# camera.net
KiCad netlist of a schematic drawn in Altium Designer
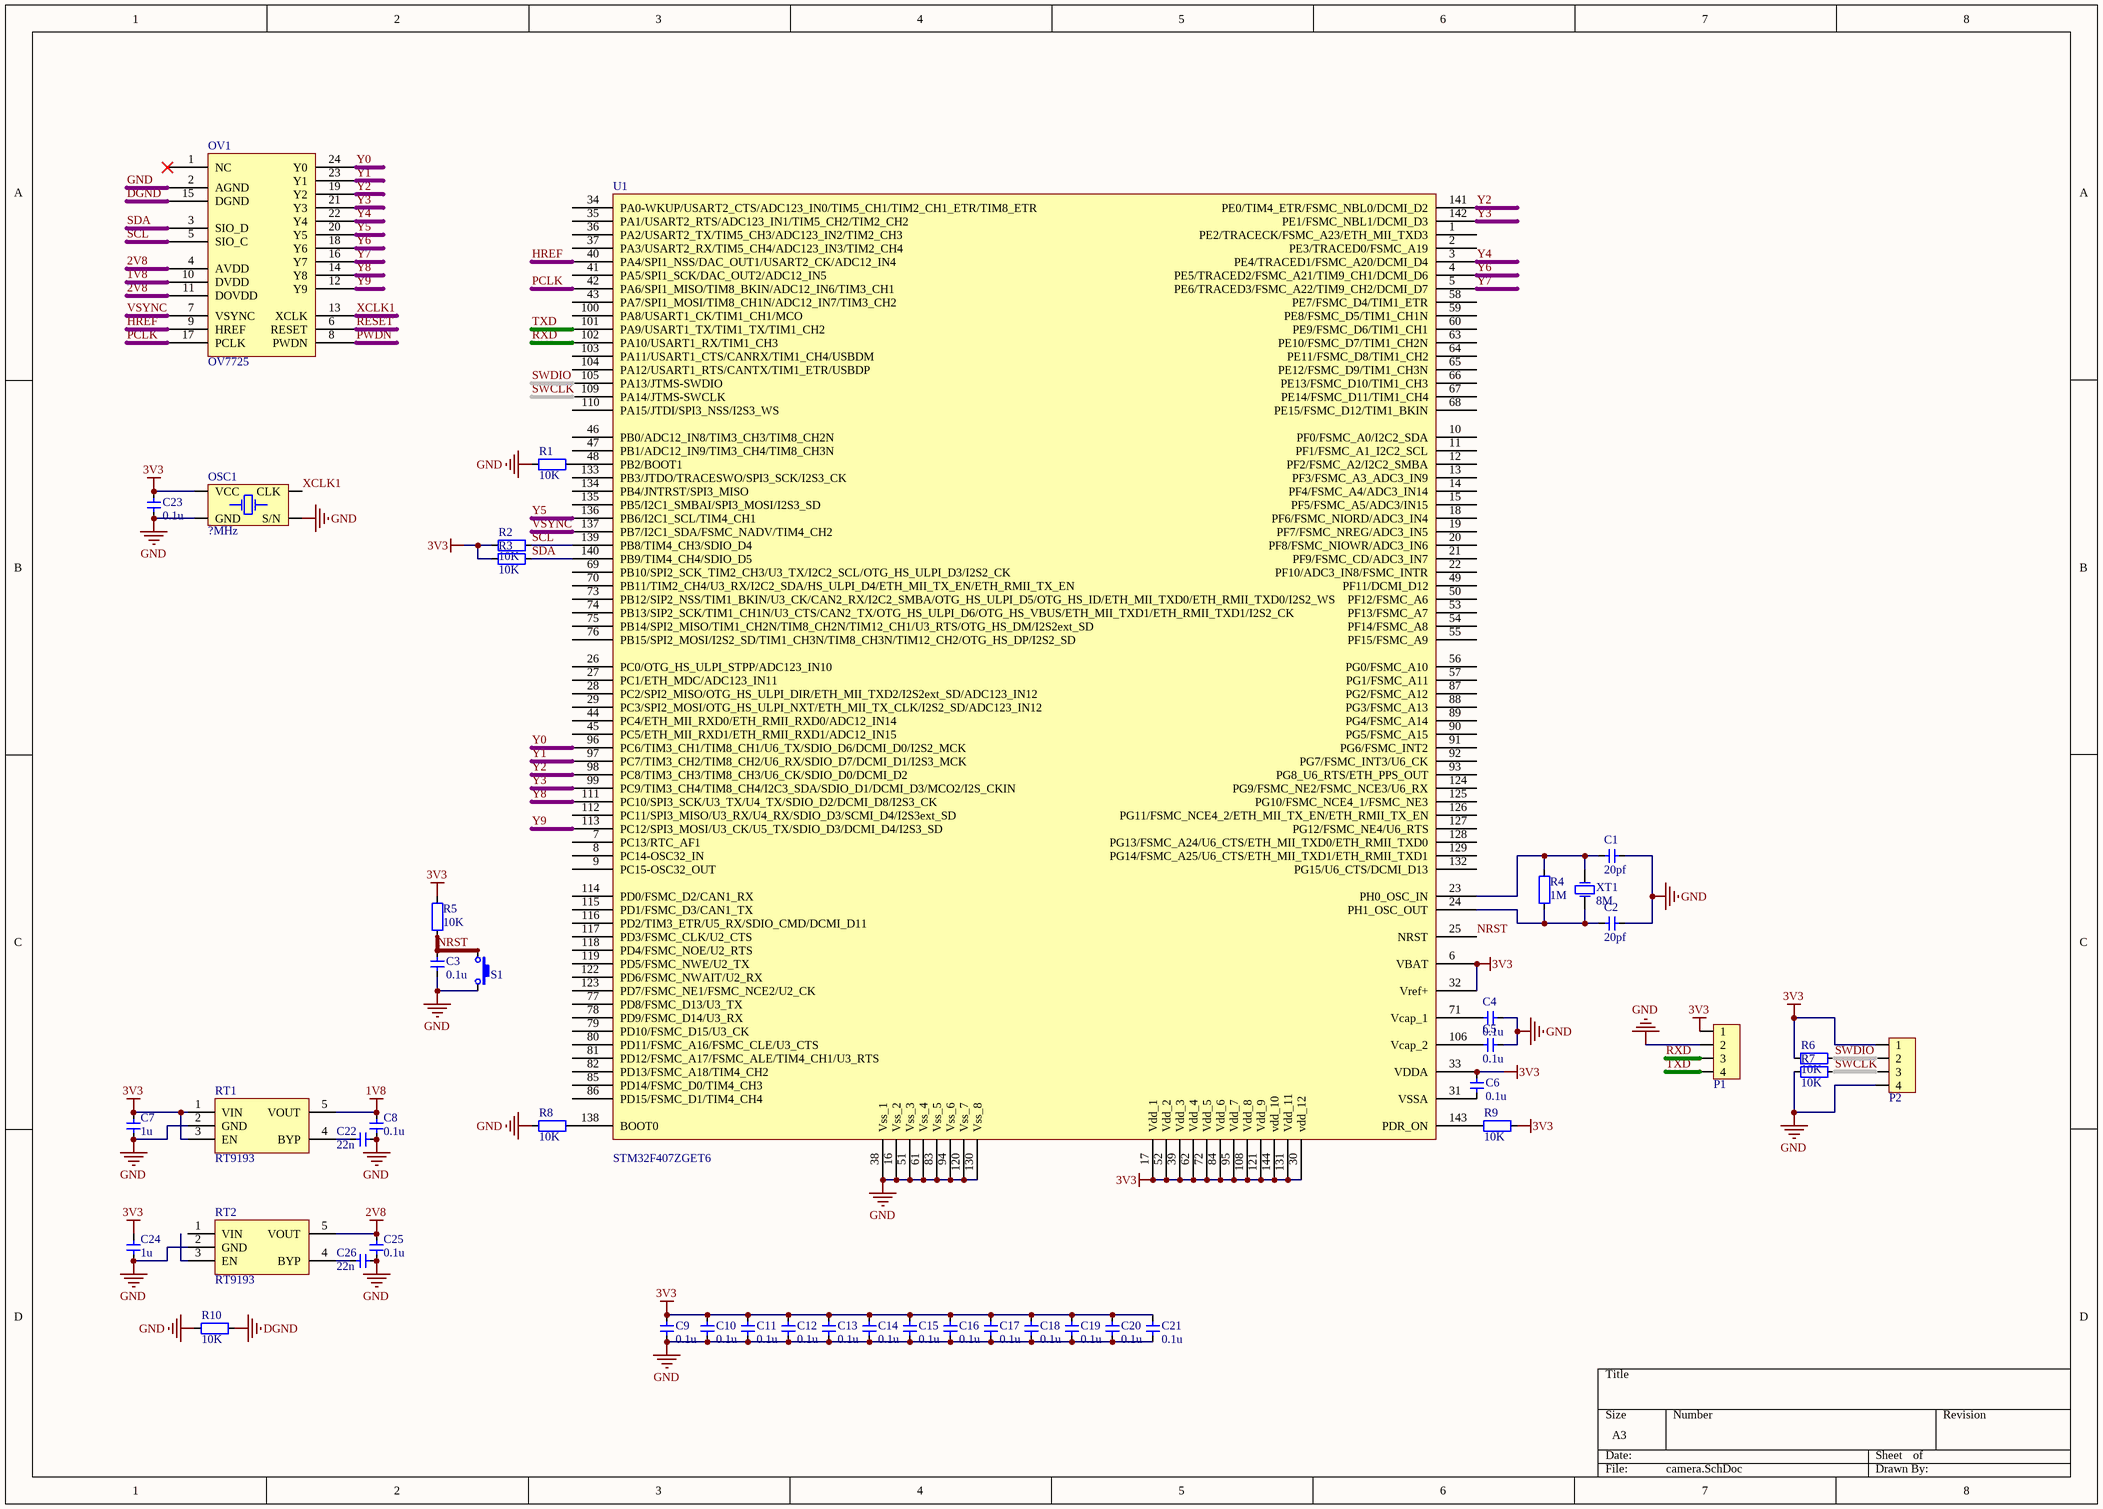
[diagram p0: camera.SchDoc]

(export (version "E")
  (design (tool "Eeschema 10.0.6"))
  (components
    (comp (ref "C1")
      (value "20pf")
      (footprint "PCB_PassiveCap:CAP_0603")
      (description "Capacitor")
      (fields (field (name "Comment") "Cap_0603"))
      (libsource (lib "SCH_Passive") (part "Cap_0603"))
    )
    (comp (ref "C2")
      (value "20pf")
      (footprint "PCB_PassiveCap:CAP_0603")
      (description "Capacitor")
      (fields (field (name "Comment") "Cap_0603"))
      (libsource (lib "SCH_Passive") (part "Cap_0603"))
    )
    (comp (ref "C3")
      (value "0.1u")
      (footprint "PCB_PassiveCap:CAP_0603")
      (description "Capacitor")
      (fields (field (name "Comment") "Cap_0603"))
      (libsource (lib "SCH_Passive") (part "Cap_0603"))
    )
    (comp (ref "C4")
      (value "0.1u")
      (footprint "PCB_PassiveCap:CAP_0603")
      (description "Capacitor")
      (fields (field (name "Comment") "Cap_0603"))
      (libsource (lib "SCH_Passive") (part "Cap_0603"))
    )
    (comp (ref "C5")
      (value "0.1u")
      (footprint "PCB_PassiveCap:CAP_0603")
      (description "Capacitor")
      (fields (field (name "Comment") "Cap_0603"))
      (libsource (lib "SCH_Passive") (part "Cap_0603"))
    )
    (comp (ref "C6")
      (value "0.1u")
      (footprint "PCB_PassiveCap:CAP_0603")
      (description "Capacitor")
      (fields (field (name "Comment") "Cap_0603"))
      (libsource (lib "SCH_Passive") (part "Cap_0603"))
    )
    (comp (ref "C7")
      (value "1u")
      (footprint "PCB_PassiveCap:CAP_0603")
      (description "Capacitor")
      (fields (field (name "Comment") "Cap_0603"))
      (libsource (lib "SCH_Passive") (part "Cap_0603"))
    )
    (comp (ref "C8")
      (value "0.1u")
      (footprint "PCB_PassiveCap:CAP_0603")
      (description "Capacitor")
      (fields (field (name "Comment") "Cap_0603"))
      (libsource (lib "SCH_Passive") (part "Cap_0603"))
    )
    (comp (ref "C9")
      (value "0.1u")
      (footprint "PCB_PassiveCap:CAP_0603")
      (description "Capacitor")
      (fields (field (name "Comment") "Cap_0603"))
      (libsource (lib "SCH_Passive") (part "Cap_0603"))
    )
    (comp (ref "C10")
      (value "0.1u")
      (footprint "PCB_PassiveCap:CAP_0603")
      (description "Capacitor")
      (fields (field (name "Comment") "Cap_0603"))
      (libsource (lib "SCH_Passive") (part "Cap_0603"))
    )
    (comp (ref "C11")
      (value "0.1u")
      (footprint "PCB_PassiveCap:CAP_0603")
      (description "Capacitor")
      (fields (field (name "Comment") "Cap_0603"))
      (libsource (lib "SCH_Passive") (part "Cap_0603"))
    )
    (comp (ref "C12")
      (value "0.1u")
      (footprint "PCB_PassiveCap:CAP_0603")
      (description "Capacitor")
      (fields (field (name "Comment") "Cap_0603"))
      (libsource (lib "SCH_Passive") (part "Cap_0603"))
    )
    (comp (ref "C13")
      (value "0.1u")
      (footprint "PCB_PassiveCap:CAP_0603")
      (description "Capacitor")
      (fields (field (name "Comment") "Cap_0603"))
      (libsource (lib "SCH_Passive") (part "Cap_0603"))
    )
    (comp (ref "C14")
      (value "0.1u")
      (footprint "PCB_PassiveCap:CAP_0603")
      (description "Capacitor")
      (fields (field (name "Comment") "Cap_0603"))
      (libsource (lib "SCH_Passive") (part "Cap_0603"))
    )
    (comp (ref "C15")
      (value "0.1u")
      (footprint "PCB_PassiveCap:CAP_0603")
      (description "Capacitor")
      (fields (field (name "Comment") "Cap_0603"))
      (libsource (lib "SCH_Passive") (part "Cap_0603"))
    )
    (comp (ref "C16")
      (value "0.1u")
      (footprint "PCB_PassiveCap:CAP_0603")
      (description "Capacitor")
      (fields (field (name "Comment") "Cap_0603"))
      (libsource (lib "SCH_Passive") (part "Cap_0603"))
    )
    (comp (ref "C17")
      (value "0.1u")
      (footprint "PCB_PassiveCap:CAP_0603")
      (description "Capacitor")
      (fields (field (name "Comment") "Cap_0603"))
      (libsource (lib "SCH_Passive") (part "Cap_0603"))
    )
    (comp (ref "C18")
      (value "0.1u")
      (footprint "PCB_PassiveCap:CAP_0603")
      (description "Capacitor")
      (fields (field (name "Comment") "Cap_0603"))
      (libsource (lib "SCH_Passive") (part "Cap_0603"))
    )
    (comp (ref "C19")
      (value "0.1u")
      (footprint "PCB_PassiveCap:CAP_0603")
      (description "Capacitor")
      (fields (field (name "Comment") "Cap_0603"))
      (libsource (lib "SCH_Passive") (part "Cap_0603"))
    )
    (comp (ref "C20")
      (value "0.1u")
      (footprint "PCB_PassiveCap:CAP_0603")
      (description "Capacitor")
      (fields (field (name "Comment") "Cap_0603"))
      (libsource (lib "SCH_Passive") (part "Cap_0603"))
    )
    (comp (ref "C21")
      (value "0.1u")
      (footprint "PCB_PassiveCap:CAP_0603")
      (description "Capacitor")
      (fields (field (name "Comment") "Cap_0603"))
      (libsource (lib "SCH_Passive") (part "Cap_0603"))
    )
    (comp (ref "C22")
      (value "22n")
      (footprint "PCB_PassiveCap:CAP_0603")
      (description "Capacitor")
      (fields (field (name "Comment") "Cap_0603"))
      (libsource (lib "SCH_Passive") (part "Cap_0603"))
    )
    (comp (ref "C23")
      (value "0.1u")
      (footprint "PCB_PassiveCap:CAP_0603")
      (description "Capacitor")
      (fields (field (name "Comment") "Cap_0603"))
      (libsource (lib "SCH_Passive") (part "Cap_0603"))
    )
    (comp (ref "C24")
      (value "1u")
      (footprint "PCB_PassiveCap:CAP_0603")
      (description "Capacitor")
      (fields (field (name "Comment") "Cap_0603"))
      (libsource (lib "SCH_Passive") (part "Cap_0603"))
    )
    (comp (ref "C25")
      (value "0.1u")
      (footprint "PCB_PassiveCap:CAP_0603")
      (description "Capacitor")
      (fields (field (name "Comment") "Cap_0603"))
      (libsource (lib "SCH_Passive") (part "Cap_0603"))
    )
    (comp (ref "C26")
      (value "22n")
      (footprint "PCB_PassiveCap:CAP_0603")
      (description "Capacitor")
      (fields (field (name "Comment") "Cap_0603"))
      (libsource (lib "SCH_Passive") (part "Cap_0603"))
    )
    (comp (ref "OSC1")
      (value "?MHz")
      (footprint "PCB_Oscillator:XT_3225_4")
      (description "Crystal Oscillator")
      (fields (field (name "Comment") "OSC_3225_4P"))
      (libsource (lib "SCH_Oscillator") (part "OSC_3225_4P"))
    )
    (comp (ref "OV1")
      (value "OV7725")
      (footprint "ov7725")
      (libsource (lib "SCH_IntegratedCircuit") (part "OV7725"))
    )
    (comp (ref "P1")
      (value "HDR1x4_2.54")
      (footprint "PCB_ConnectorHDR:HDR1X4_2.54_90")
      (description "Header")
      (libsource (lib "SCH_ConnectorHDR") (part "HDR1x4_2.54"))
    )
    (comp (ref "P2")
      (value "HDR1x4_2.54")
      (footprint "PCB_ConnectorHDR:HDR1X4_2.54_90")
      (description "Header")
      (libsource (lib "SCH_ConnectorHDR") (part "HDR1x4_2.54"))
    )
    (comp (ref "R1")
      (value "10K")
      (footprint "PCB_PassiveRes:RES_0603")
      (description "Resistor")
      (fields (field (name "Comment") "Res_0603"))
      (libsource (lib "") (part "Res_0603_2"))
    )
    (comp (ref "R2")
      (value "10K")
      (footprint "PCB_PassiveRes:RES_0603")
      (description "Resistor")
      (fields (field (name "Comment") "Res_0603"))
      (libsource (lib "") (part "Res_0603_1"))
    )
    (comp (ref "R3")
      (value "10K")
      (footprint "PCB_PassiveRes:RES_0603")
      (description "Resistor")
      (fields (field (name "Comment") "Res_0603"))
      (libsource (lib "") (part "Res_0603_1"))
    )
    (comp (ref "R4")
      (value "1M")
      (footprint "PCB_PassiveRes:RES_0603")
      (description "Resistor")
      (fields (field (name "Comment") "Res_0603"))
      (libsource (lib "SCH_Passive") (part "Res_0603"))
    )
    (comp (ref "R5")
      (value "10K")
      (footprint "PCB_PassiveRes:RES_0603")
      (description "Resistor")
      (fields (field (name "Comment") "Res_0603"))
      (libsource (lib "SCH_Passive") (part "Res_0603"))
    )
    (comp (ref "R6")
      (value "10K")
      (footprint "PCB_PassiveRes:RES_0603")
      (description "Resistor")
      (fields (field (name "Comment") "Res_0603"))
      (libsource (lib "") (part "Res_0603_2"))
    )
    (comp (ref "R7")
      (value "10K")
      (footprint "PCB_PassiveRes:RES_0603")
      (description "Resistor")
      (fields (field (name "Comment") "Res_0603"))
      (libsource (lib "") (part "Res_0603_2"))
    )
    (comp (ref "R8")
      (value "10K")
      (footprint "PCB_PassiveRes:RES_0603")
      (description "Resistor")
      (fields (field (name "Comment") "Res_0603"))
      (libsource (lib "") (part "Res_0603_1"))
    )
    (comp (ref "R9")
      (value "10K")
      (footprint "PCB_PassiveRes:RES_0603")
      (description "Resistor")
      (fields (field (name "Comment") "Res_0603"))
      (libsource (lib "") (part "Res_0603_1"))
    )
    (comp (ref "R10")
      (value "10K")
      (footprint "PCB_PassiveRes:RES_0603")
      (description "Resistor")
      (fields (field (name "Comment") "Res_0603"))
      (libsource (lib "") (part "Res_0603_1"))
    )
    (comp (ref "RT1")
      (value "RT9193")
      (footprint "PCB_IntegratedCircuit:SOT23-5")
      (description "Power")
      (libsource (lib "SCH_IntegratedCircuit") (part "RT9193"))
    )
    (comp (ref "RT2")
      (value "RT9193")
      (footprint "PCB_IntegratedCircuit:SOT23-5")
      (description "Power")
      (libsource (lib "SCH_IntegratedCircuit") (part "RT9193"))
    )
    (comp (ref "S1")
      (value "ButtonTACT_3x4x2_180")
      (footprint "PCB_Switch:ButtonTACT_3x4x2_180H")
      (description "Button")
      (libsource (lib "SCH_Switch") (part "ButtonTACT_3x4x2_180"))
    )
    (comp (ref "U1")
      (value "STM32F407ZGET6")
      (footprint "LQFP_P0.5_144")
      (libsource (lib "STM32F407VGT6") (part "Component_1"))
    )
    (comp (ref "XT1")
      (value "8M")
      (footprint "PCB_Oscillator:XT_5032_2")
      (description "Crystal Oscillator")
      (fields (field (name "Comment") "XTAL_5032_2P"))
      (libsource (lib "SCH_Oscillator") (part "XTAL_5032_2P"))
    )
  )
  (nets
    (net (code "1") (name "/HREF") (class "Default")
      (node (ref "OV1") (pin "9") (pinfunction "HREF_9") (pintype "passive"))
      (node (ref "U1") (pin "40") (pinfunction "PA4/SPI1_NSS/DAC_OUT1/USART2_CK/ADC12_IN4_40") (pintype "passive"))
    )
    (net (code "2") (name "/NRST") (class "Default")
      (node (ref "C3") (pin "2") (pinfunction "2_2") (pintype "passive"))
      (node (ref "R5") (pin "2") (pinfunction "2_2") (pintype "passive"))
      (node (ref "S1") (pin "1") (pinfunction "1_1") (pintype "passive"))
      (node (ref "U1") (pin "25") (pinfunction "NRST_25") (pintype "passive"))
    )
    (net (code "3") (name "/PCLK") (class "Default")
      (node (ref "OV1") (pin "17") (pinfunction "PCLK_17") (pintype "passive"))
      (node (ref "U1") (pin "42") (pinfunction "PA6/SPI1_MISO/TIM8_BKIN/ADC12_IN6/TIM3_CH1_42") (pintype "passive"))
    )
    (net (code "4") (name "/PWDN") (class "Default")
      (node (ref "OV1") (pin "8") (pinfunction "PWDN_8") (pintype "passive"))
    )
    (net (code "5") (name "/RESET") (class "Default")
      (node (ref "OV1") (pin "6") (pinfunction "RESET_6") (pintype "passive"))
    )
    (net (code "6") (name "/RXD") (class "Default")
      (node (ref "P1") (pin "3") (pinfunction "3_3") (pintype "passive"))
      (node (ref "U1") (pin "102") (pinfunction "PA10/USART1_RX/TIM1_CH3_102") (pintype "passive"))
    )
    (net (code "7") (name "/SCL") (class "Default")
      (node (ref "OV1") (pin "5") (pinfunction "SIO_C_5") (pintype "passive"))
      (node (ref "R2") (pin "2") (pinfunction "2_2") (pintype "passive"))
      (node (ref "U1") (pin "139") (pinfunction "PB8/TIM4_CH3/SDIO_D4_139") (pintype "passive"))
    )
    (net (code "8") (name "/SDA") (class "Default")
      (node (ref "OV1") (pin "3") (pinfunction "SIO_D_3") (pintype "passive"))
      (node (ref "R3") (pin "2") (pinfunction "2_2") (pintype "passive"))
      (node (ref "U1") (pin "140") (pinfunction "PB9/TIM4_CH4/SDIO_D5_140") (pintype "passive"))
    )
    (net (code "9") (name "/SWCLK") (class "Default")
      (node (ref "P2") (pin "3") (pinfunction "3_3") (pintype "passive"))
      (node (ref "R7") (pin "1") (pinfunction "1_1") (pintype "passive"))
      (node (ref "U1") (pin "109") (pinfunction "PA14/JTMS-SWCLK_109") (pintype "passive"))
    )
    (net (code "10") (name "/SWDIO") (class "Default")
      (node (ref "P2") (pin "2") (pinfunction "2_2") (pintype "passive"))
      (node (ref "R6") (pin "1") (pinfunction "1_1") (pintype "passive"))
      (node (ref "U1") (pin "105") (pinfunction "PA13/JTMS-SWDIO_105") (pintype "passive"))
    )
    (net (code "11") (name "/TXD") (class "Default")
      (node (ref "P1") (pin "4") (pinfunction "4_4") (pintype "passive"))
      (node (ref "U1") (pin "101") (pinfunction "PA9/USART1_TX/TIM1_TX/TIM1_CH2_101") (pintype "passive"))
    )
    (net (code "12") (name "/VSYNC") (class "Default")
      (node (ref "OV1") (pin "7") (pinfunction "VSYNC_7") (pintype "passive"))
      (node (ref "U1") (pin "137") (pinfunction "PB7/I2C1_SDA/FSMC_NADV/TIM4_CH2_137") (pintype "passive"))
    )
    (net (code "13") (name "/XCLK1") (class "Default")
      (node (ref "OSC1") (pin "3") (pinfunction "CLK_3") (pintype "passive"))
      (node (ref "OV1") (pin "13") (pinfunction "XCLK_13") (pintype "passive"))
    )
    (net (code "14") (name "/Y0") (class "Default")
      (node (ref "OV1") (pin "24") (pinfunction "Y0_24") (pintype "passive"))
      (node (ref "U1") (pin "96") (pinfunction "PC6/TIM3_CH1/TIM8_CH1/U6_TX/SDIO_D6/DCMI_D0/I2S2_MCK_96") (pintype "passive"))
    )
    (net (code "15") (name "/Y1") (class "Default")
      (node (ref "OV1") (pin "23") (pinfunction "Y1_23") (pintype "passive"))
      (node (ref "U1") (pin "97") (pinfunction "PC7/TIM3_CH2/TIM8_CH2/U6_RX/SDIO_D7/DCMI_D1/I2S3_MCK_97") (pintype "passive"))
    )
    (net (code "16") (name "/Y2") (class "Default")
      (node (ref "OV1") (pin "19") (pinfunction "Y2_19") (pintype "passive"))
      (node (ref "U1") (pin "141") (pinfunction "PE0/TIM4_ETR/FSMC_NBL0/DCMI_D2_141") (pintype "passive"))
      (node (ref "U1") (pin "98") (pinfunction "PC8/TIM3_CH3/TIM8_CH3/U6_CK/SDIO_D0/DCMI_D2_98") (pintype "passive"))
    )
    (net (code "17") (name "/Y3") (class "Default")
      (node (ref "OV1") (pin "21") (pinfunction "Y3_21") (pintype "passive"))
      (node (ref "U1") (pin "142") (pinfunction "PE1/FSMC_NBL1/DCMI_D3_142") (pintype "passive"))
      (node (ref "U1") (pin "99") (pinfunction "PC9/TIM3_CH4/TIM8_CH4/I2C3_SDA/SDIO_D1/DCMI_D3/MCO2/I2S_CKIN_99") (pintype "passive"))
    )
    (net (code "18") (name "/Y4") (class "Default")
      (node (ref "OV1") (pin "22") (pinfunction "Y4_22") (pintype "passive"))
      (node (ref "U1") (pin "3") (pinfunction "PE4/TRACED1/FSMC_A20/DCMI_D4_3") (pintype "passive"))
    )
    (net (code "19") (name "/Y5") (class "Default")
      (node (ref "OV1") (pin "20") (pinfunction "Y5_20") (pintype "passive"))
      (node (ref "U1") (pin "136") (pinfunction "PB6/I2C1_SCL/TIM4_CH1_136") (pintype "passive"))
    )
    (net (code "20") (name "/Y6") (class "Default")
      (node (ref "OV1") (pin "18") (pinfunction "Y6_18") (pintype "passive"))
      (node (ref "U1") (pin "4") (pinfunction "PE5/TRACED2/FSMC_A21/TIM9_CH1/DCMI_D6_4") (pintype "passive"))
    )
    (net (code "21") (name "/Y7") (class "Default")
      (node (ref "OV1") (pin "16") (pinfunction "Y7_16") (pintype "passive"))
      (node (ref "U1") (pin "5") (pinfunction "PE6/TRACED3/FSMC_A22/TIM9_CH2/DCMI_D7_5") (pintype "passive"))
    )
    (net (code "22") (name "/Y8") (class "Default")
      (node (ref "OV1") (pin "14") (pinfunction "Y8_14") (pintype "passive"))
      (node (ref "U1") (pin "111") (pinfunction "PC10/SPI3_SCK/U3_TX/U4_TX/SDIO_D2/DCMI_D8/I2S3_CK_111") (pintype "passive"))
    )
    (net (code "23") (name "/Y9") (class "Default")
      (node (ref "OV1") (pin "12") (pinfunction "Y9_12") (pintype "passive"))
      (node (ref "U1") (pin "113") (pinfunction "PC12/SPI3_MOSI/U3_CK/U5_TX/SDIO_D3/DCMI_D4/I2S3_SD_113") (pintype "passive"))
    )
    (net (code "24") (name "1V8") (class "Default")
      (node (ref "C8") (pin "2") (pinfunction "2_2") (pintype "passive"))
      (node (ref "OV1") (pin "10") (pinfunction "DVDD_10") (pintype "passive"))
      (node (ref "RT1") (pin "5") (pinfunction "VOUT_5") (pintype "passive"))
    )
    (net (code "25") (name "2V8") (class "Default")
      (node (ref "C25") (pin "2") (pinfunction "2_2") (pintype "passive"))
      (node (ref "OV1") (pin "11") (pinfunction "DOVDD_11") (pintype "passive"))
      (node (ref "OV1") (pin "4") (pinfunction "AVDD_4") (pintype "passive"))
      (node (ref "RT2") (pin "5") (pinfunction "VOUT_5") (pintype "passive"))
    )
    (net (code "26") (name "3V3") (class "Default")
      (node (ref "C10") (pin "2") (pinfunction "2_2") (pintype "passive"))
      (node (ref "C11") (pin "2") (pinfunction "2_2") (pintype "passive"))
      (node (ref "C12") (pin "2") (pinfunction "2_2") (pintype "passive"))
      (node (ref "C13") (pin "2") (pinfunction "2_2") (pintype "passive"))
      (node (ref "C14") (pin "2") (pinfunction "2_2") (pintype "passive"))
      (node (ref "C15") (pin "2") (pinfunction "2_2") (pintype "passive"))
      (node (ref "C16") (pin "2") (pinfunction "2_2") (pintype "passive"))
      (node (ref "C17") (pin "2") (pinfunction "2_2") (pintype "passive"))
      (node (ref "C18") (pin "2") (pinfunction "2_2") (pintype "passive"))
      (node (ref "C19") (pin "2") (pinfunction "2_2") (pintype "passive"))
      (node (ref "C20") (pin "2") (pinfunction "2_2") (pintype "passive"))
      (node (ref "C21") (pin "2") (pinfunction "2_2") (pintype "passive"))
      (node (ref "C23") (pin "2") (pinfunction "2_2") (pintype "passive"))
      (node (ref "C24") (pin "2") (pinfunction "2_2") (pintype "passive"))
      (node (ref "C6") (pin "1") (pinfunction "1_1") (pintype "passive"))
      (node (ref "C7") (pin "2") (pinfunction "2_2") (pintype "passive"))
      (node (ref "C9") (pin "2") (pinfunction "2_2") (pintype "passive"))
      (node (ref "OSC1") (pin "4") (pinfunction "VCC_4") (pintype "passive"))
      (node (ref "P1") (pin "1") (pinfunction "1_1") (pintype "passive"))
      (node (ref "P2") (pin "1") (pinfunction "1_1") (pintype "passive"))
      (node (ref "R2") (pin "1") (pinfunction "1_1") (pintype "passive"))
      (node (ref "R3") (pin "1") (pinfunction "1_1") (pintype "passive"))
      (node (ref "R5") (pin "1") (pinfunction "1_1") (pintype "passive"))
      (node (ref "R6") (pin "2") (pinfunction "2_2") (pintype "passive"))
      (node (ref "R9") (pin "2") (pinfunction "2_2") (pintype "passive"))
      (node (ref "RT1") (pin "1") (pinfunction "VIN_1") (pintype "passive"))
      (node (ref "RT1") (pin "3") (pinfunction "EN_3") (pintype "power_in"))
      (node (ref "U1") (pin "108") (pinfunction "Vdd_8_108") (pintype "passive"))
      (node (ref "U1") (pin "121") (pinfunction "Vdd_9_121") (pintype "passive"))
      (node (ref "U1") (pin "131") (pinfunction "Vdd_11_131") (pintype "passive"))
      (node (ref "U1") (pin "144") (pinfunction "vdd_10_144") (pintype "passive"))
      (node (ref "U1") (pin "17") (pinfunction "Vdd_1_17") (pintype "passive"))
      (node (ref "U1") (pin "30") (pinfunction "vdd_12_30") (pintype "passive"))
      (node (ref "U1") (pin "32") (pinfunction "Vref+_32") (pintype "passive"))
      (node (ref "U1") (pin "33") (pinfunction "VDDA_33") (pintype "passive"))
      (node (ref "U1") (pin "39") (pinfunction "Vdd_3_39") (pintype "passive"))
      (node (ref "U1") (pin "52") (pinfunction "Vdd_2_52") (pintype "passive"))
      (node (ref "U1") (pin "6") (pinfunction "VBAT_6") (pintype "passive"))
      (node (ref "U1") (pin "62") (pinfunction "Vdd_4_62") (pintype "passive"))
      (node (ref "U1") (pin "72") (pinfunction "Vdd_5_72") (pintype "passive"))
      (node (ref "U1") (pin "84") (pinfunction "Vdd_6_84") (pintype "passive"))
      (node (ref "U1") (pin "95") (pinfunction "Vdd_7_95") (pintype "passive"))
    )
    (net (code "27") (name "DGND") (class "Default")
      (node (ref "OV1") (pin "15") (pinfunction "DGND_15") (pintype "passive"))
      (node (ref "R10") (pin "2") (pinfunction "2_2") (pintype "passive"))
    )
    (net (code "28") (name "GND") (class "Default")
      (node (ref "C1") (pin "1") (pinfunction "1_1") (pintype "passive"))
      (node (ref "C10") (pin "1") (pinfunction "1_1") (pintype "passive"))
      (node (ref "C11") (pin "1") (pinfunction "1_1") (pintype "passive"))
      (node (ref "C12") (pin "1") (pinfunction "1_1") (pintype "passive"))
      (node (ref "C13") (pin "1") (pinfunction "1_1") (pintype "passive"))
      (node (ref "C14") (pin "1") (pinfunction "1_1") (pintype "passive"))
      (node (ref "C15") (pin "1") (pinfunction "1_1") (pintype "passive"))
      (node (ref "C16") (pin "1") (pinfunction "1_1") (pintype "passive"))
      (node (ref "C17") (pin "1") (pinfunction "1_1") (pintype "passive"))
      (node (ref "C18") (pin "1") (pinfunction "1_1") (pintype "passive"))
      (node (ref "C19") (pin "1") (pinfunction "1_1") (pintype "passive"))
      (node (ref "C2") (pin "1") (pinfunction "1_1") (pintype "passive"))
      (node (ref "C20") (pin "1") (pinfunction "1_1") (pintype "passive"))
      (node (ref "C21") (pin "1") (pinfunction "1_1") (pintype "passive"))
      (node (ref "C22") (pin "1") (pinfunction "1_1") (pintype "passive"))
      (node (ref "C23") (pin "1") (pinfunction "1_1") (pintype "passive"))
      (node (ref "C24") (pin "1") (pinfunction "1_1") (pintype "passive"))
      (node (ref "C25") (pin "1") (pinfunction "1_1") (pintype "passive"))
      (node (ref "C26") (pin "1") (pinfunction "1_1") (pintype "passive"))
      (node (ref "C3") (pin "1") (pinfunction "1_1") (pintype "passive"))
      (node (ref "C4") (pin "1") (pinfunction "1_1") (pintype "passive"))
      (node (ref "C5") (pin "1") (pinfunction "1_1") (pintype "passive"))
      (node (ref "C7") (pin "1") (pinfunction "1_1") (pintype "passive"))
      (node (ref "C8") (pin "1") (pinfunction "1_1") (pintype "passive"))
      (node (ref "C9") (pin "1") (pinfunction "1_1") (pintype "passive"))
      (node (ref "OSC1") (pin "1") (pinfunction "S/N_1") (pintype "passive"))
      (node (ref "OSC1") (pin "2") (pinfunction "GND_2") (pintype "passive"))
      (node (ref "OV1") (pin "2") (pinfunction "AGND_2") (pintype "passive"))
      (node (ref "P1") (pin "2") (pinfunction "2_2") (pintype "passive"))
      (node (ref "P2") (pin "4") (pinfunction "4_4") (pintype "passive"))
      (node (ref "R1") (pin "2") (pinfunction "2_2") (pintype "passive"))
      (node (ref "R10") (pin "1") (pinfunction "1_1") (pintype "passive"))
      (node (ref "R7") (pin "2") (pinfunction "2_2") (pintype "passive"))
      (node (ref "R8") (pin "1") (pinfunction "1_1") (pintype "passive"))
      (node (ref "RT1") (pin "2") (pinfunction "GND_2") (pintype "passive"))
      (node (ref "RT2") (pin "2") (pinfunction "GND_2") (pintype "passive"))
      (node (ref "S1") (pin "2") (pinfunction "2_2") (pintype "passive"))
      (node (ref "U1") (pin "120") (pinfunction "Vss_7_120") (pintype "passive"))
      (node (ref "U1") (pin "130") (pinfunction "Vss_8_130") (pintype "passive"))
      (node (ref "U1") (pin "16") (pinfunction "Vss_2_16") (pintype "passive"))
      (node (ref "U1") (pin "38") (pinfunction "Vss_1_38") (pintype "passive"))
      (node (ref "U1") (pin "51") (pinfunction "Vss_3_51") (pintype "passive"))
      (node (ref "U1") (pin "61") (pinfunction "Vss_4_61") (pintype "passive"))
      (node (ref "U1") (pin "83") (pinfunction "Vss_5_83") (pintype "passive"))
      (node (ref "U1") (pin "94") (pinfunction "Vss_6_94") (pintype "passive"))
    )
    (net (code "29") (name "Net-(RT1-BYP)") (class "Default")
      (node (ref "C22") (pin "2") (pinfunction "2_2") (pintype "passive"))
      (node (ref "RT1") (pin "4") (pinfunction "BYP_4") (pintype "passive"))
    )
    (net (code "30") (name "Net-(RT2-BYP)") (class "Default")
      (node (ref "C26") (pin "2") (pinfunction "2_2") (pintype "passive"))
      (node (ref "RT2") (pin "4") (pinfunction "BYP_4") (pintype "passive"))
    )
    (net (code "31") (name "Net-(U1-BOOT0)") (class "Default")
      (node (ref "R8") (pin "2") (pinfunction "2_2") (pintype "passive"))
      (node (ref "U1") (pin "138") (pinfunction "BOOT0_138") (pintype "passive"))
    )
    (net (code "32") (name "Net-(U1-PB2{slash}BOOT1)") (class "Default")
      (node (ref "R1") (pin "1") (pinfunction "1_1") (pintype "passive"))
      (node (ref "U1") (pin "48") (pinfunction "PB2/BOOT1_48") (pintype "passive"))
    )
    (net (code "33") (name "Net-(U1-PDR_ON)") (class "Default")
      (node (ref "R9") (pin "1") (pinfunction "1_1") (pintype "passive"))
      (node (ref "U1") (pin "143") (pinfunction "PDR_ON_143") (pintype "passive"))
    )
    (net (code "34") (name "Net-(U1-PH0_OSC_IN)") (class "Default")
      (node (ref "C1") (pin "2") (pinfunction "2_2") (pintype "passive"))
      (node (ref "R4") (pin "1") (pinfunction "1_1") (pintype "passive"))
      (node (ref "U1") (pin "23") (pinfunction "PH0_OSC_IN_23") (pintype "passive"))
      (node (ref "XT1") (pin "1") (pinfunction "OSC1_1") (pintype "passive"))
    )
    (net (code "35") (name "Net-(U1-PH1_OSC_OUT)") (class "Default")
      (node (ref "C2") (pin "2") (pinfunction "2_2") (pintype "passive"))
      (node (ref "R4") (pin "2") (pinfunction "2_2") (pintype "passive"))
      (node (ref "U1") (pin "24") (pinfunction "PH1_OSC_OUT_24") (pintype "passive"))
      (node (ref "XT1") (pin "2") (pinfunction "OSC2_2") (pintype "passive"))
    )
    (net (code "36") (name "Net-(U1-VSSA)") (class "Default")
      (node (ref "C6") (pin "2") (pinfunction "2_2") (pintype "passive"))
      (node (ref "U1") (pin "31") (pinfunction "VSSA_31") (pintype "passive"))
    )
    (net (code "37") (name "Net-(U1-Vcap_1)") (class "Default")
      (node (ref "C4") (pin "2") (pinfunction "2_2") (pintype "passive"))
      (node (ref "U1") (pin "71") (pinfunction "Vcap_1_71") (pintype "passive"))
    )
    (net (code "38") (name "Net-(U1-Vcap_2)") (class "Default")
      (node (ref "C5") (pin "2") (pinfunction "2_2") (pintype "passive"))
      (node (ref "U1") (pin "106") (pinfunction "Vcap_2_106") (pintype "passive"))
    )
    (net (code "39") (name "unconnected-(OV1-NC-Pad1)") (class "Default")
      (node (ref "OV1") (pin "1") (pinfunction "NC_1") (pintype "passive+no_connect"))
    )
    (net (code "40") (name "unconnected-(RT2-EN-Pad3)") (class "Default")
      (node (ref "RT2") (pin "3") (pinfunction "EN_3") (pintype "power_in"))
    )
    (net (code "41") (name "unconnected-(RT2-VIN-Pad1)") (class "Default")
      (node (ref "RT2") (pin "1") (pinfunction "VIN_1") (pintype "passive"))
    )
    (net (code "42") (name "unconnected-(U1-PA0-WKUP{slash}USART2_CTS{slash}ADC123_IN0{slash}TIM5_CH1{slash}TIM2_CH1_ETR{slash}TIM8_ETR-Pad34)") (class "Default")
      (node (ref "U1") (pin "34") (pinfunction "PA0-WKUP/USART2_CTS/ADC123_IN0/TIM5_CH1/TIM2_CH1_ETR/TIM8_ETR_34") (pintype "passive"))
    )
    (net (code "43") (name "unconnected-(U1-PA1{slash}USART2_RTS{slash}ADC123_IN1{slash}TIM5_CH2{slash}TIM2_CH2-Pad35)") (class "Default")
      (node (ref "U1") (pin "35") (pinfunction "PA1/USART2_RTS/ADC123_IN1/TIM5_CH2/TIM2_CH2_35") (pintype "passive"))
    )
    (net (code "44") (name "unconnected-(U1-PA2{slash}USART2_TX{slash}TIM5_CH3{slash}ADC123_IN2{slash}TIM2_CH3-Pad36)") (class "Default")
      (node (ref "U1") (pin "36") (pinfunction "PA2/USART2_TX/TIM5_CH3/ADC123_IN2/TIM2_CH3_36") (pintype "passive"))
    )
    (net (code "45") (name "unconnected-(U1-PA3{slash}USART2_RX{slash}TIM5_CH4{slash}ADC123_IN3{slash}TIM2_CH4-Pad37)") (class "Default")
      (node (ref "U1") (pin "37") (pinfunction "PA3/USART2_RX/TIM5_CH4/ADC123_IN3/TIM2_CH4_37") (pintype "passive"))
    )
    (net (code "46") (name "unconnected-(U1-PA5{slash}SPI1_SCK{slash}DAC_OUT2{slash}ADC12_IN5-Pad41)") (class "Default")
      (node (ref "U1") (pin "41") (pinfunction "PA5/SPI1_SCK/DAC_OUT2/ADC12_IN5_41") (pintype "passive"))
    )
    (net (code "47") (name "unconnected-(U1-PA7{slash}SPI1_MOSI{slash}TIM8_CH1N{slash}ADC12_IN7{slash}TIM3_CH2-Pad43)") (class "Default")
      (node (ref "U1") (pin "43") (pinfunction "PA7/SPI1_MOSI/TIM8_CH1N/ADC12_IN7/TIM3_CH2_43") (pintype "passive"))
    )
    (net (code "48") (name "unconnected-(U1-PA8{slash}USART1_CK{slash}TIM1_CH1{slash}MCO-Pad100)") (class "Default")
      (node (ref "U1") (pin "100") (pinfunction "PA8/USART1_CK/TIM1_CH1/MCO_100") (pintype "passive"))
    )
    (net (code "49") (name "unconnected-(U1-PA11{slash}USART1_CTS{slash}CANRX{slash}TIM1_CH4{slash}USBDM-Pad103)") (class "Default")
      (node (ref "U1") (pin "103") (pinfunction "PA11/USART1_CTS/CANRX/TIM1_CH4/USBDM_103") (pintype "passive"))
    )
    (net (code "50") (name "unconnected-(U1-PA12{slash}USART1_RTS{slash}CANTX{slash}TIM1_ETR{slash}USBDP-Pad104)") (class "Default")
      (node (ref "U1") (pin "104") (pinfunction "PA12/USART1_RTS/CANTX/TIM1_ETR/USBDP_104") (pintype "passive"))
    )
    (net (code "51") (name "unconnected-(U1-PA15{slash}JTDI{slash}SPI3_NSS{slash}I2S3_WS-Pad110)") (class "Default")
      (node (ref "U1") (pin "110") (pinfunction "PA15/JTDI/SPI3_NSS/I2S3_WS_110") (pintype "passive"))
    )
    (net (code "52") (name "unconnected-(U1-PB0{slash}ADC12_IN8{slash}TIM3_CH3{slash}TIM8_CH2N-Pad46)") (class "Default")
      (node (ref "U1") (pin "46") (pinfunction "PB0/ADC12_IN8/TIM3_CH3/TIM8_CH2N_46") (pintype "passive"))
    )
    (net (code "53") (name "unconnected-(U1-PB1{slash}ADC12_IN9{slash}TIM3_CH4{slash}TIM8_CH3N-Pad47)") (class "Default")
      (node (ref "U1") (pin "47") (pinfunction "PB1/ADC12_IN9/TIM3_CH4/TIM8_CH3N_47") (pintype "passive"))
    )
    (net (code "54") (name "unconnected-(U1-PB3{slash}JTDO{slash}TRACESWO{slash}SPI3_SCK{slash}I2S3_CK-Pad133)") (class "Default")
      (node (ref "U1") (pin "133") (pinfunction "PB3/JTDO/TRACESWO/SPI3_SCK/I2S3_CK_133") (pintype "passive"))
    )
    (net (code "55") (name "unconnected-(U1-PB4{slash}JNTRST{slash}SPI3_MISO-Pad134)") (class "Default")
      (node (ref "U1") (pin "134") (pinfunction "PB4/JNTRST/SPI3_MISO_134") (pintype "passive"))
    )
    (net (code "56") (name "unconnected-(U1-PB5{slash}I2C1_SMBAI{slash}SPI3_MOSI{slash}I2S3_SD-Pad135)") (class "Default")
      (node (ref "U1") (pin "135") (pinfunction "PB5/I2C1_SMBAI/SPI3_MOSI/I2S3_SD_135") (pintype "passive"))
    )
    (net (code "57") (name "unconnected-(U1-PB10{slash}SPI2_SCK_TIM2_CH3{slash}U3_TX{slash}I2C2_SCL{slash}OTG_HS_ULPI_D3{slash}I2S2_CK-Pad69)") (class "Default")
      (node (ref "U1") (pin "69") (pinfunction "PB10/SPI2_SCK_TIM2_CH3/U3_TX/I2C2_SCL/OTG_HS_ULPI_D3/I2S2_CK_69") (pintype "passive"))
    )
    (net (code "58") (name "unconnected-(U1-PB11{slash}TIM2_CH4{slash}U3_RX{slash}I2C2_SDA{slash}HS_ULPI_D4{slash}ETH_MII_TX_EN{slash}ETH_RMII_TX_EN-Pad70)") (class "Default")
      (node (ref "U1") (pin "70") (pinfunction "PB11/TIM2_CH4/U3_RX/I2C2_SDA/HS_ULPI_D4/ETH_MII_TX_EN/ETH_RMII_TX_EN_70") (pintype "passive"))
    )
    (net (code "59") (name "unconnected-(U1-PB12{slash}SIP2_NSS{slash}TIM1_BKIN{slash}U3_CK{slash}CAN2_RX{slash}I2C2_SMBA{slash}OTG_HS_ULPI_D5{slash}OTG_HS_ID{slash}ETH_MII_TXD0{slash}ETH_RMII_TXD0{slash}I2S2_WS-Pad73)") (class "Default")
      (node (ref "U1") (pin "73") (pinfunction "PB12/SIP2_NSS/TIM1_BKIN/U3_CK/CAN2_RX/I2C2_SMBA/OTG_HS_ULPI_D5/OTG_HS_ID/ETH_MII_TXD0/ETH_RMII_TXD0/I2S2_WS_73") (pintype "passive"))
    )
    (net (code "60") (name "unconnected-(U1-PB13{slash}SIP2_SCK{slash}TIM1_CH1N{slash}U3_CTS{slash}CAN2_TX{slash}OTG_HS_ULPI_D6{slash}OTG_HS_VBUS{slash}ETH_MII_TXD1{slash}ETH_RMII_TXD1{slash}I2S2_CK-Pad74)") (class "Default")
      (node (ref "U1") (pin "74") (pinfunction "PB13/SIP2_SCK/TIM1_CH1N/U3_CTS/CAN2_TX/OTG_HS_ULPI_D6/OTG_HS_VBUS/ETH_MII_TXD1/ETH_RMII_TXD1/I2S2_CK_74") (pintype "passive"))
    )
    (net (code "61") (name "unconnected-(U1-PB14{slash}SPI2_MISO{slash}TIM1_CH2N{slash}TIM8_CH2N{slash}TIM12_CH1{slash}U3_RTS{slash}OTG_HS_DM{slash}I2S2ext_SD-Pad75)") (class "Default")
      (node (ref "U1") (pin "75") (pinfunction "PB14/SPI2_MISO/TIM1_CH2N/TIM8_CH2N/TIM12_CH1/U3_RTS/OTG_HS_DM/I2S2ext_SD_75") (pintype "passive"))
    )
    (net (code "62") (name "unconnected-(U1-PB15{slash}SPI2_MOSI{slash}I2S2_SD{slash}TIM1_CH3N{slash}TIM8_CH3N{slash}TIM12_CH2{slash}OTG_HS_DP{slash}I2S2_SD-Pad76)") (class "Default")
      (node (ref "U1") (pin "76") (pinfunction "PB15/SPI2_MOSI/I2S2_SD/TIM1_CH3N/TIM8_CH3N/TIM12_CH2/OTG_HS_DP/I2S2_SD_76") (pintype "passive"))
    )
    (net (code "63") (name "unconnected-(U1-PC0{slash}OTG_HS_ULPI_STPP{slash}ADC123_IN10-Pad26)") (class "Default")
      (node (ref "U1") (pin "26") (pinfunction "PC0/OTG_HS_ULPI_STPP/ADC123_IN10_26") (pintype "passive"))
    )
    (net (code "64") (name "unconnected-(U1-PC1{slash}ETH_MDC{slash}ADC123_IN11-Pad27)") (class "Default")
      (node (ref "U1") (pin "27") (pinfunction "PC1/ETH_MDC/ADC123_IN11_27") (pintype "passive"))
    )
    (net (code "65") (name "unconnected-(U1-PC2{slash}SPI2_MISO{slash}OTG_HS_ULPI_DIR{slash}ETH_MII_TXD2{slash}I2S2ext_SD{slash}ADC123_IN12-Pad28)") (class "Default")
      (node (ref "U1") (pin "28") (pinfunction "PC2/SPI2_MISO/OTG_HS_ULPI_DIR/ETH_MII_TXD2/I2S2ext_SD/ADC123_IN12_28") (pintype "passive"))
    )
    (net (code "66") (name "unconnected-(U1-PC3{slash}SPI2_MOSI{slash}OTG_HS_ULPI_NXT{slash}ETH_MII_TX_CLK{slash}I2S2_SD{slash}ADC123_IN12-Pad29)") (class "Default")
      (node (ref "U1") (pin "29") (pinfunction "PC3/SPI2_MOSI/OTG_HS_ULPI_NXT/ETH_MII_TX_CLK/I2S2_SD/ADC123_IN12_29") (pintype "passive"))
    )
    (net (code "67") (name "unconnected-(U1-PC4{slash}ETH_MII_RXD0{slash}ETH_RMII_RXD0{slash}ADC12_IN14-Pad44)") (class "Default")
      (node (ref "U1") (pin "44") (pinfunction "PC4/ETH_MII_RXD0/ETH_RMII_RXD0/ADC12_IN14_44") (pintype "passive"))
    )
    (net (code "68") (name "unconnected-(U1-PC5{slash}ETH_MII_RXD1{slash}ETH_RMII_RXD1{slash}ADC12_IN15-Pad45)") (class "Default")
      (node (ref "U1") (pin "45") (pinfunction "PC5/ETH_MII_RXD1/ETH_RMII_RXD1/ADC12_IN15_45") (pintype "passive"))
    )
    (net (code "69") (name "unconnected-(U1-PC11{slash}SPI3_MISO{slash}U3_RX{slash}U4_RX{slash}SDIO_D3{slash}SCMI_D4{slash}I2S3ext_SD-Pad112)") (class "Default")
      (node (ref "U1") (pin "112") (pinfunction "PC11/SPI3_MISO/U3_RX/U4_RX/SDIO_D3/SCMI_D4/I2S3ext_SD_112") (pintype "passive"))
    )
    (net (code "70") (name "unconnected-(U1-PC13{slash}RTC_AF1-Pad7)") (class "Default")
      (node (ref "U1") (pin "7") (pinfunction "PC13/RTC_AF1_7") (pintype "passive"))
    )
    (net (code "71") (name "unconnected-(U1-PC14-OSC32_IN-Pad8)") (class "Default")
      (node (ref "U1") (pin "8") (pinfunction "PC14-OSC32_IN_8") (pintype "passive"))
    )
    (net (code "72") (name "unconnected-(U1-PC15-OSC32_OUT-Pad9)") (class "Default")
      (node (ref "U1") (pin "9") (pinfunction "PC15-OSC32_OUT_9") (pintype "passive"))
    )
    (net (code "73") (name "unconnected-(U1-PD0{slash}FSMC_D2{slash}CAN1_RX-Pad114)") (class "Default")
      (node (ref "U1") (pin "114") (pinfunction "PD0/FSMC_D2/CAN1_RX_114") (pintype "passive"))
    )
    (net (code "74") (name "unconnected-(U1-PD1{slash}FSMC_D3{slash}CAN1_TX-Pad115)") (class "Default")
      (node (ref "U1") (pin "115") (pinfunction "PD1/FSMC_D3/CAN1_TX_115") (pintype "passive"))
    )
    (net (code "75") (name "unconnected-(U1-PD2{slash}TIM3_ETR{slash}U5_RX{slash}SDIO_CMD{slash}DCMI_D11-Pad116)") (class "Default")
      (node (ref "U1") (pin "116") (pinfunction "PD2/TIM3_ETR/U5_RX/SDIO_CMD/DCMI_D11_116") (pintype "passive"))
    )
    (net (code "76") (name "unconnected-(U1-PD3{slash}FSMC_CLK{slash}U2_CTS-Pad117)") (class "Default")
      (node (ref "U1") (pin "117") (pinfunction "PD3/FSMC_CLK/U2_CTS_117") (pintype "passive"))
    )
    (net (code "77") (name "unconnected-(U1-PD4{slash}FSMC_NOE{slash}U2_RTS-Pad118)") (class "Default")
      (node (ref "U1") (pin "118") (pinfunction "PD4/FSMC_NOE/U2_RTS_118") (pintype "passive"))
    )
    (net (code "78") (name "unconnected-(U1-PD5{slash}FSMC_NWE{slash}U2_TX-Pad119)") (class "Default")
      (node (ref "U1") (pin "119") (pinfunction "PD5/FSMC_NWE/U2_TX_119") (pintype "passive"))
    )
    (net (code "79") (name "unconnected-(U1-PD6{slash}FSMC_NWAIT{slash}U2_RX-Pad122)") (class "Default")
      (node (ref "U1") (pin "122") (pinfunction "PD6/FSMC_NWAIT/U2_RX_122") (pintype "passive"))
    )
    (net (code "80") (name "unconnected-(U1-PD7{slash}FSMC_NE1{slash}FSMC_NCE2{slash}U2_CK-Pad123)") (class "Default")
      (node (ref "U1") (pin "123") (pinfunction "PD7/FSMC_NE1/FSMC_NCE2/U2_CK_123") (pintype "passive"))
    )
    (net (code "81") (name "unconnected-(U1-PD8{slash}FSMC_D13{slash}U3_TX-Pad77)") (class "Default")
      (node (ref "U1") (pin "77") (pinfunction "PD8/FSMC_D13/U3_TX_77") (pintype "passive"))
    )
    (net (code "82") (name "unconnected-(U1-PD9{slash}FSMC_D14{slash}U3_RX-Pad78)") (class "Default")
      (node (ref "U1") (pin "78") (pinfunction "PD9/FSMC_D14/U3_RX_78") (pintype "passive"))
    )
    (net (code "83") (name "unconnected-(U1-PD10{slash}FSMC_D15{slash}U3_CK-Pad79)") (class "Default")
      (node (ref "U1") (pin "79") (pinfunction "PD10/FSMC_D15/U3_CK_79") (pintype "passive"))
    )
    (net (code "84") (name "unconnected-(U1-PD11{slash}FSMC_A16{slash}FSMC_CLE{slash}U3_CTS-Pad80)") (class "Default")
      (node (ref "U1") (pin "80") (pinfunction "PD11/FSMC_A16/FSMC_CLE/U3_CTS_80") (pintype "passive"))
    )
    (net (code "85") (name "unconnected-(U1-PD12{slash}FSMC_A17{slash}FSMC_ALE{slash}TIM4_CH1{slash}U3_RTS-Pad81)") (class "Default")
      (node (ref "U1") (pin "81") (pinfunction "PD12/FSMC_A17/FSMC_ALE/TIM4_CH1/U3_RTS_81") (pintype "passive"))
    )
    (net (code "86") (name "unconnected-(U1-PD13{slash}FSMC_A18{slash}TIM4_CH2-Pad82)") (class "Default")
      (node (ref "U1") (pin "82") (pinfunction "PD13/FSMC_A18/TIM4_CH2_82") (pintype "passive"))
    )
    (net (code "87") (name "unconnected-(U1-PD14{slash}FSMC_D0{slash}TIM4_CH3-Pad85)") (class "Default")
      (node (ref "U1") (pin "85") (pinfunction "PD14/FSMC_D0/TIM4_CH3_85") (pintype "passive"))
    )
    (net (code "88") (name "unconnected-(U1-PD15{slash}FSMC_D1{slash}TIM4_CH4-Pad86)") (class "Default")
      (node (ref "U1") (pin "86") (pinfunction "PD15/FSMC_D1/TIM4_CH4_86") (pintype "passive"))
    )
    (net (code "89") (name "unconnected-(U1-PE2{slash}TRACECK{slash}FSMC_A23{slash}ETH_MII_TXD3-Pad1)") (class "Default")
      (node (ref "U1") (pin "1") (pinfunction "PE2/TRACECK/FSMC_A23/ETH_MII_TXD3_1") (pintype "passive"))
    )
    (net (code "90") (name "unconnected-(U1-PE3{slash}TRACED0{slash}FSMC_A19-Pad2)") (class "Default")
      (node (ref "U1") (pin "2") (pinfunction "PE3/TRACED0/FSMC_A19_2") (pintype "passive"))
    )
    (net (code "91") (name "unconnected-(U1-PE7{slash}FSMC_D4{slash}TIM1_ETR-Pad58)") (class "Default")
      (node (ref "U1") (pin "58") (pinfunction "PE7/FSMC_D4/TIM1_ETR_58") (pintype "passive"))
    )
    (net (code "92") (name "unconnected-(U1-PE8{slash}FSMC_D5{slash}TIM1_CH1N-Pad59)") (class "Default")
      (node (ref "U1") (pin "59") (pinfunction "PE8/FSMC_D5/TIM1_CH1N_59") (pintype "passive"))
    )
    (net (code "93") (name "unconnected-(U1-PE9{slash}FSMC_D6{slash}TIM1_CH1-Pad60)") (class "Default")
      (node (ref "U1") (pin "60") (pinfunction "PE9/FSMC_D6/TIM1_CH1_60") (pintype "passive"))
    )
    (net (code "94") (name "unconnected-(U1-PE10{slash}FSMC_D7{slash}TIM1_CH2N-Pad63)") (class "Default")
      (node (ref "U1") (pin "63") (pinfunction "PE10/FSMC_D7/TIM1_CH2N_63") (pintype "passive"))
    )
    (net (code "95") (name "unconnected-(U1-PE11{slash}FSMC_D8{slash}TIM1_CH2-Pad64)") (class "Default")
      (node (ref "U1") (pin "64") (pinfunction "PE11/FSMC_D8/TIM1_CH2_64") (pintype "passive"))
    )
    (net (code "96") (name "unconnected-(U1-PE12{slash}FSMC_D9{slash}TIM1_CH3N-Pad65)") (class "Default")
      (node (ref "U1") (pin "65") (pinfunction "PE12/FSMC_D9/TIM1_CH3N_65") (pintype "passive"))
    )
    (net (code "97") (name "unconnected-(U1-PE13{slash}FSMC_D10{slash}TIM1_CH3-Pad66)") (class "Default")
      (node (ref "U1") (pin "66") (pinfunction "PE13/FSMC_D10/TIM1_CH3_66") (pintype "passive"))
    )
    (net (code "98") (name "unconnected-(U1-PE14{slash}FSMC_D11{slash}TIM1_CH4-Pad67)") (class "Default")
      (node (ref "U1") (pin "67") (pinfunction "PE14/FSMC_D11/TIM1_CH4_67") (pintype "passive"))
    )
    (net (code "99") (name "unconnected-(U1-PE15{slash}FSMC_D12{slash}TIM1_BKIN-Pad68)") (class "Default")
      (node (ref "U1") (pin "68") (pinfunction "PE15/FSMC_D12/TIM1_BKIN_68") (pintype "passive"))
    )
    (net (code "100") (name "unconnected-(U1-PF0{slash}FSMC_A0{slash}I2C2_SDA-Pad10)") (class "Default")
      (node (ref "U1") (pin "10") (pinfunction "PF0/FSMC_A0/I2C2_SDA_10") (pintype "passive"))
    )
    (net (code "101") (name "unconnected-(U1-PF1{slash}FSMC_A1_I2C2_SCL-Pad11)") (class "Default")
      (node (ref "U1") (pin "11") (pinfunction "PF1/FSMC_A1_I2C2_SCL_11") (pintype "passive"))
    )
    (net (code "102") (name "unconnected-(U1-PF2{slash}FSMC_A2{slash}I2C2_SMBA-Pad12)") (class "Default")
      (node (ref "U1") (pin "12") (pinfunction "PF2/FSMC_A2/I2C2_SMBA_12") (pintype "passive"))
    )
    (net (code "103") (name "unconnected-(U1-PF3{slash}FSMC_A3_ADC3_IN9-Pad13)") (class "Default")
      (node (ref "U1") (pin "13") (pinfunction "PF3/FSMC_A3_ADC3_IN9_13") (pintype "passive"))
    )
    (net (code "104") (name "unconnected-(U1-PF4{slash}FSMC_A4{slash}ADC3_IN14-Pad14)") (class "Default")
      (node (ref "U1") (pin "14") (pinfunction "PF4/FSMC_A4/ADC3_IN14_14") (pintype "passive"))
    )
    (net (code "105") (name "unconnected-(U1-PF5{slash}FSMC_A5{slash}ADC3{slash}IN15-Pad15)") (class "Default")
      (node (ref "U1") (pin "15") (pinfunction "PF5/FSMC_A5/ADC3/IN15_15") (pintype "passive"))
    )
    (net (code "106") (name "unconnected-(U1-PF6{slash}FSMC_NIORD{slash}ADC3_IN4-Pad18)") (class "Default")
      (node (ref "U1") (pin "18") (pinfunction "PF6/FSMC_NIORD/ADC3_IN4_18") (pintype "passive"))
    )
    (net (code "107") (name "unconnected-(U1-PF7{slash}FSMC_NREG{slash}ADC3_IN5-Pad19)") (class "Default")
      (node (ref "U1") (pin "19") (pinfunction "PF7/FSMC_NREG/ADC3_IN5_19") (pintype "passive"))
    )
    (net (code "108") (name "unconnected-(U1-PF8{slash}FSMC_NIOWR{slash}ADC3_IN6-Pad20)") (class "Default")
      (node (ref "U1") (pin "20") (pinfunction "PF8/FSMC_NIOWR/ADC3_IN6_20") (pintype "passive"))
    )
    (net (code "109") (name "unconnected-(U1-PF9{slash}FSMC_CD{slash}ADC3_IN7-Pad21)") (class "Default")
      (node (ref "U1") (pin "21") (pinfunction "PF9/FSMC_CD/ADC3_IN7_21") (pintype "passive"))
    )
    (net (code "110") (name "unconnected-(U1-PF10{slash}ADC3_IN8{slash}FSMC_INTR-Pad22)") (class "Default")
      (node (ref "U1") (pin "22") (pinfunction "PF10/ADC3_IN8/FSMC_INTR_22") (pintype "passive"))
    )
    (net (code "111") (name "unconnected-(U1-PF11{slash}DCMI_D12-Pad49)") (class "Default")
      (node (ref "U1") (pin "49") (pinfunction "PF11/DCMI_D12_49") (pintype "passive"))
    )
    (net (code "112") (name "unconnected-(U1-PF12{slash}FSMC_A6-Pad50)") (class "Default")
      (node (ref "U1") (pin "50") (pinfunction "PF12/FSMC_A6_50") (pintype "passive"))
    )
    (net (code "113") (name "unconnected-(U1-PF13{slash}FSMC_A7-Pad53)") (class "Default")
      (node (ref "U1") (pin "53") (pinfunction "PF13/FSMC_A7_53") (pintype "passive"))
    )
    (net (code "114") (name "unconnected-(U1-PF14{slash}FSMC_A8-Pad54)") (class "Default")
      (node (ref "U1") (pin "54") (pinfunction "PF14/FSMC_A8_54") (pintype "passive"))
    )
    (net (code "115") (name "unconnected-(U1-PF15{slash}FSMC_A9-Pad55)") (class "Default")
      (node (ref "U1") (pin "55") (pinfunction "PF15/FSMC_A9_55") (pintype "passive"))
    )
    (net (code "116") (name "unconnected-(U1-PG0{slash}FSMC_A10-Pad56)") (class "Default")
      (node (ref "U1") (pin "56") (pinfunction "PG0/FSMC_A10_56") (pintype "passive"))
    )
    (net (code "117") (name "unconnected-(U1-PG1{slash}FSMC_A11-Pad57)") (class "Default")
      (node (ref "U1") (pin "57") (pinfunction "PG1/FSMC_A11_57") (pintype "passive"))
    )
    (net (code "118") (name "unconnected-(U1-PG2{slash}FSMC_A12-Pad87)") (class "Default")
      (node (ref "U1") (pin "87") (pinfunction "PG2/FSMC_A12_87") (pintype "passive"))
    )
    (net (code "119") (name "unconnected-(U1-PG3{slash}FSMC_A13-Pad88)") (class "Default")
      (node (ref "U1") (pin "88") (pinfunction "PG3/FSMC_A13_88") (pintype "passive"))
    )
    (net (code "120") (name "unconnected-(U1-PG4{slash}FSMC_A14-Pad89)") (class "Default")
      (node (ref "U1") (pin "89") (pinfunction "PG4/FSMC_A14_89") (pintype "passive"))
    )
    (net (code "121") (name "unconnected-(U1-PG5{slash}FSMC_A15-Pad90)") (class "Default")
      (node (ref "U1") (pin "90") (pinfunction "PG5/FSMC_A15_90") (pintype "passive"))
    )
    (net (code "122") (name "unconnected-(U1-PG6{slash}FSMC_INT2-Pad91)") (class "Default")
      (node (ref "U1") (pin "91") (pinfunction "PG6/FSMC_INT2_91") (pintype "passive"))
    )
    (net (code "123") (name "unconnected-(U1-PG7{slash}FSMC_INT3{slash}U6_CK-Pad92)") (class "Default")
      (node (ref "U1") (pin "92") (pinfunction "PG7/FSMC_INT3/U6_CK_92") (pintype "passive"))
    )
    (net (code "124") (name "unconnected-(U1-PG8_U6_RTS{slash}ETH_PPS_OUT-Pad93)") (class "Default")
      (node (ref "U1") (pin "93") (pinfunction "PG8_U6_RTS/ETH_PPS_OUT_93") (pintype "passive"))
    )
    (net (code "125") (name "unconnected-(U1-PG9{slash}FSMC_NE2{slash}FSMC_NCE3{slash}U6_RX-Pad124)") (class "Default")
      (node (ref "U1") (pin "124") (pinfunction "PG9/FSMC_NE2/FSMC_NCE3/U6_RX_124") (pintype "passive"))
    )
    (net (code "126") (name "unconnected-(U1-PG10{slash}FSMC_NCE4_1{slash}FSMC_NE3-Pad125)") (class "Default")
      (node (ref "U1") (pin "125") (pinfunction "PG10/FSMC_NCE4_1/FSMC_NE3_125") (pintype "passive"))
    )
    (net (code "127") (name "unconnected-(U1-PG11{slash}FSMC_NCE4_2{slash}ETH_MII_TX_EN{slash}ETH_RMII_TX_EN-Pad126)") (class "Default")
      (node (ref "U1") (pin "126") (pinfunction "PG11/FSMC_NCE4_2/ETH_MII_TX_EN/ETH_RMII_TX_EN_126") (pintype "passive"))
    )
    (net (code "128") (name "unconnected-(U1-PG12{slash}FSMC_NE4{slash}U6_RTS-Pad127)") (class "Default")
      (node (ref "U1") (pin "127") (pinfunction "PG12/FSMC_NE4/U6_RTS_127") (pintype "passive"))
    )
    (net (code "129") (name "unconnected-(U1-PG13{slash}FSMC_A24{slash}U6_CTS{slash}ETH_MII_TXD0{slash}ETH_RMII_TXD0-Pad128)") (class "Default")
      (node (ref "U1") (pin "128") (pinfunction "PG13/FSMC_A24/U6_CTS/ETH_MII_TXD0/ETH_RMII_TXD0_128") (pintype "passive"))
    )
    (net (code "130") (name "unconnected-(U1-PG14{slash}FSMC_A25{slash}U6_CTS{slash}ETH_MII_TXD1{slash}ETH_RMII_TXD1-Pad129)") (class "Default")
      (node (ref "U1") (pin "129") (pinfunction "PG14/FSMC_A25/U6_CTS/ETH_MII_TXD1/ETH_RMII_TXD1_129") (pintype "passive"))
    )
    (net (code "131") (name "unconnected-(U1-PG15{slash}U6_CTS{slash}DCMI_D13-Pad132)") (class "Default")
      (node (ref "U1") (pin "132") (pinfunction "PG15/U6_CTS/DCMI_D13_132") (pintype "passive"))
    )
  )
)
